# sdram.net
KiCad netlist of a schematic drawn in Altium Designer
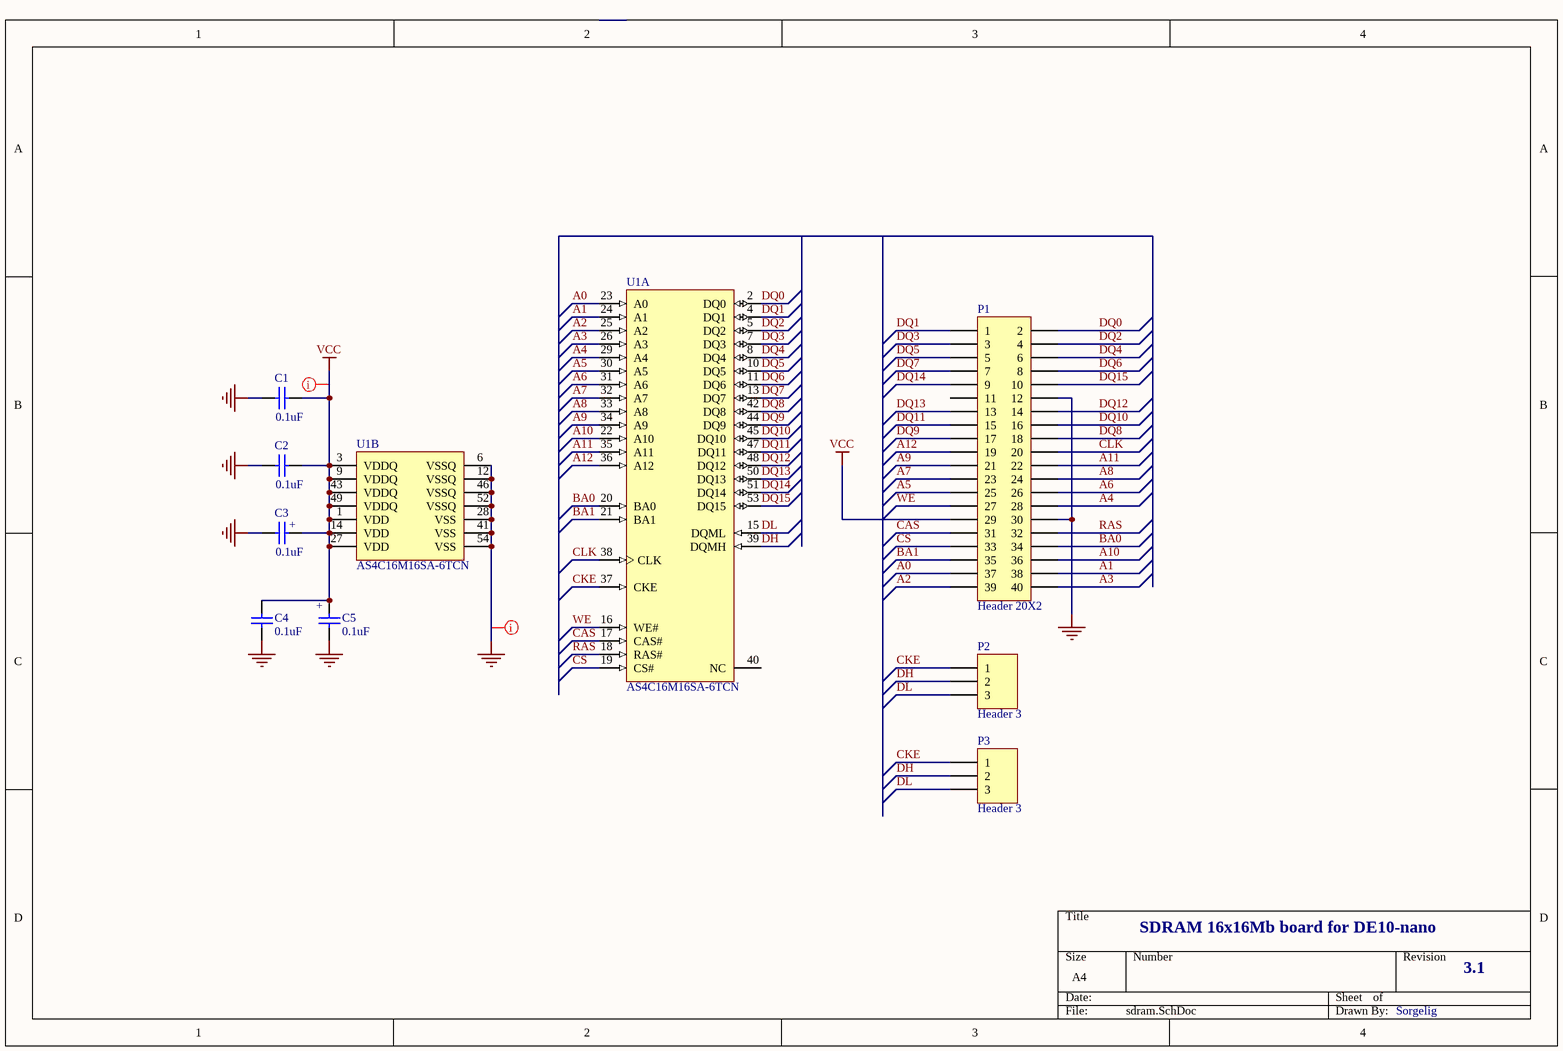
[diagram p0: sdram.SchDoc]

(export (version "E")
  (design (tool "Eeschema 10.0.6"))
  (components
    (comp (ref "C1")
      (value "0.1uF")
      (footprint "0805")
      (description "Ceramic Chip Capacitor - Standard")
      (fields (field (name "Comment") "C0805") (field (name "PUBLISHER") "Altium Limited"))
      (libsource (lib "KEMET Chip Capacitor") (part "C0805"))
    )
    (comp (ref "C2")
      (value "0.1uF")
      (footprint "0805")
      (description "Ceramic Chip Capacitor - Standard")
      (fields (field (name "Comment") "C0805") (field (name "PUBLISHER") "Altium Limited"))
      (libsource (lib "KEMET Chip Capacitor") (part "C0805"))
    )
    (comp (ref "C3")
      (value "+")
      (footprint "0805")
      (description "Ceramic Chip Capacitor - Standard")
      (fields (field (name "ALTIUM_VALUE") "0.1uF") (field (name "PUBLISHER") "Altium Limited"))
      (libsource (lib "KEMET Chip Capacitor") (part "C0805"))
    )
    (comp (ref "C4")
      (value "0.1uF")
      (footprint "0805")
      (description "Ceramic Chip Capacitor - Standard")
      (fields (field (name "Comment") "C0805") (field (name "PUBLISHER") "Altium Limited"))
      (libsource (lib "KEMET Chip Capacitor") (part "C0805"))
    )
    (comp (ref "C5")
      (value "+")
      (footprint "0805")
      (description "Ceramic Chip Capacitor - Standard")
      (fields (field (name "ALTIUM_VALUE") "0.1uF") (field (name "PUBLISHER") "Altium Limited"))
      (libsource (lib "KEMET Chip Capacitor") (part "C0805"))
    )
    (comp (ref "P1")
      (value "Header 20X2")
      (footprint "HDR2X20")
      (description "Header, 20-Pin, Dual row")
      (fields (field (name "PUBLISHER") "Altium Limited"))
      (libsource (lib "Miscellaneous Connectors") (part "Header 20X2"))
    )
    (comp (ref "P2")
      (value "Header 3")
      (footprint "HDR1X3")
      (description "Header, 3-Pin")
      (fields (field (name "PUBLISHER") "Altium Limited"))
      (libsource (lib "Miscellaneous Connectors") (part "Header 3"))
    )
    (comp (ref "P3")
      (value "Header 3")
      (footprint "HDR1X3")
      (description "Header, 3-Pin")
      (fields (field (name "PUBLISHER") "Altium Limited"))
      (libsource (lib "Miscellaneous Connectors") (part "Header 3"))
    )
    (comp (ref "U1")
      (value "AS4C16M16SA-6TCN")
      (footprint "MICT-P-54_N")
      (description "256Mb PC133 SDR SDRAM, 16Mb x 16, 6ns, 3.3V, 0 to 70 degC, 54-Pin TSOP, Pb-Free")
      (fields (field (name "VOLTAGE") "3.3V ") (field (name "MANUFACTURER") "Micron"))
      (libsource (lib "Micron Memory SDRAM") (part "MT48LC16M16A2P-6A"))
    )
  )
  (nets
    (net (code "1") (name "/A0") (class "Default")
      (node (ref "P1") (pin "37") (pinfunction "37_37") (pintype "passive"))
      (node (ref "U1") (pin "23") (pinfunction "A0_23") (pintype "input"))
    )
    (net (code "2") (name "/A1") (class "Default")
      (node (ref "P1") (pin "38") (pinfunction "38_38") (pintype "passive"))
      (node (ref "U1") (pin "24") (pinfunction "A1_24") (pintype "input"))
    )
    (net (code "3") (name "/A2") (class "Default")
      (node (ref "P1") (pin "39") (pinfunction "39_39") (pintype "passive"))
      (node (ref "U1") (pin "25") (pinfunction "A2_25") (pintype "input"))
    )
    (net (code "4") (name "/A3") (class "Default")
      (node (ref "P1") (pin "40") (pinfunction "40_40") (pintype "passive"))
      (node (ref "U1") (pin "26") (pinfunction "A3_26") (pintype "input"))
    )
    (net (code "5") (name "/A4") (class "Default")
      (node (ref "P1") (pin "28") (pinfunction "28_28") (pintype "passive"))
      (node (ref "U1") (pin "29") (pinfunction "A4_29") (pintype "input"))
    )
    (net (code "6") (name "/A5") (class "Default")
      (node (ref "P1") (pin "25") (pinfunction "25_25") (pintype "passive"))
      (node (ref "U1") (pin "30") (pinfunction "A5_30") (pintype "input"))
    )
    (net (code "7") (name "/A6") (class "Default")
      (node (ref "P1") (pin "26") (pinfunction "26_26") (pintype "passive"))
      (node (ref "U1") (pin "31") (pinfunction "A6_31") (pintype "input"))
    )
    (net (code "8") (name "/A7") (class "Default")
      (node (ref "P1") (pin "23") (pinfunction "23_23") (pintype "passive"))
      (node (ref "U1") (pin "32") (pinfunction "A7_32") (pintype "input"))
    )
    (net (code "9") (name "/A8") (class "Default")
      (node (ref "P1") (pin "24") (pinfunction "24_24") (pintype "passive"))
      (node (ref "U1") (pin "33") (pinfunction "A8_33") (pintype "input"))
    )
    (net (code "10") (name "/A9") (class "Default")
      (node (ref "P1") (pin "21") (pinfunction "21_21") (pintype "passive"))
      (node (ref "U1") (pin "34") (pinfunction "A9_34") (pintype "input"))
    )
    (net (code "11") (name "/A10") (class "Default")
      (node (ref "P1") (pin "36") (pinfunction "36_36") (pintype "passive"))
      (node (ref "U1") (pin "22") (pinfunction "A10_22") (pintype "input"))
    )
    (net (code "12") (name "/A11") (class "Default")
      (node (ref "P1") (pin "22") (pinfunction "22_22") (pintype "passive"))
      (node (ref "U1") (pin "35") (pinfunction "A11_35") (pintype "input"))
    )
    (net (code "13") (name "/A12") (class "Default")
      (node (ref "P1") (pin "19") (pinfunction "19_19") (pintype "passive"))
      (node (ref "U1") (pin "36") (pinfunction "A12_36") (pintype "input"))
    )
    (net (code "14") (name "/BA0") (class "Default")
      (node (ref "P1") (pin "34") (pinfunction "34_34") (pintype "passive"))
      (node (ref "U1") (pin "20") (pinfunction "BA0_20") (pintype "input"))
    )
    (net (code "15") (name "/BA1") (class "Default")
      (node (ref "P1") (pin "35") (pinfunction "35_35") (pintype "passive"))
      (node (ref "U1") (pin "21") (pinfunction "BA1_21") (pintype "input"))
    )
    (net (code "16") (name "/CAS") (class "Default")
      (node (ref "P1") (pin "31") (pinfunction "31_31") (pintype "passive"))
      (node (ref "U1") (pin "17") (pinfunction "CAS#_17") (pintype "input"))
    )
    (net (code "17") (name "/CKE") (class "Default")
      (node (ref "P2") (pin "1") (pinfunction "1_1") (pintype "passive"))
      (node (ref "P3") (pin "1") (pinfunction "1_1") (pintype "passive"))
      (node (ref "U1") (pin "37") (pinfunction "CKE_37") (pintype "input"))
    )
    (net (code "18") (name "/CLK") (class "Default")
      (node (ref "P1") (pin "20") (pinfunction "20_20") (pintype "passive"))
      (node (ref "U1") (pin "38") (pinfunction "CLK_38") (pintype "input"))
    )
    (net (code "19") (name "/CS") (class "Default")
      (node (ref "P1") (pin "33") (pinfunction "33_33") (pintype "passive"))
      (node (ref "U1") (pin "19") (pinfunction "CS#_19") (pintype "input"))
    )
    (net (code "20") (name "/DH") (class "Default")
      (node (ref "P2") (pin "2") (pinfunction "2_2") (pintype "passive"))
      (node (ref "P3") (pin "2") (pinfunction "2_2") (pintype "passive"))
      (node (ref "U1") (pin "39") (pinfunction "DQMH_39") (pintype "input"))
    )
    (net (code "21") (name "/DL") (class "Default")
      (node (ref "P2") (pin "3") (pinfunction "3_3") (pintype "passive"))
      (node (ref "P3") (pin "3") (pinfunction "3_3") (pintype "passive"))
      (node (ref "U1") (pin "15") (pinfunction "DQML_15") (pintype "input"))
    )
    (net (code "22") (name "/DQ0") (class "Default")
      (node (ref "P1") (pin "2") (pinfunction "2_2") (pintype "passive"))
      (node (ref "U1") (pin "2") (pinfunction "DQ0_2") (pintype "bidirectional"))
    )
    (net (code "23") (name "/DQ1") (class "Default")
      (node (ref "P1") (pin "1") (pinfunction "1_1") (pintype "passive"))
      (node (ref "U1") (pin "4") (pinfunction "DQ1_4") (pintype "bidirectional"))
    )
    (net (code "24") (name "/DQ2") (class "Default")
      (node (ref "P1") (pin "4") (pinfunction "4_4") (pintype "passive"))
      (node (ref "U1") (pin "5") (pinfunction "DQ2_5") (pintype "bidirectional"))
    )
    (net (code "25") (name "/DQ3") (class "Default")
      (node (ref "P1") (pin "3") (pinfunction "3_3") (pintype "passive"))
      (node (ref "U1") (pin "7") (pinfunction "DQ3_7") (pintype "bidirectional"))
    )
    (net (code "26") (name "/DQ4") (class "Default")
      (node (ref "P1") (pin "6") (pinfunction "6_6") (pintype "passive"))
      (node (ref "U1") (pin "8") (pinfunction "DQ4_8") (pintype "bidirectional"))
    )
    (net (code "27") (name "/DQ5") (class "Default")
      (node (ref "P1") (pin "5") (pinfunction "5_5") (pintype "passive"))
      (node (ref "U1") (pin "10") (pinfunction "DQ5_10") (pintype "bidirectional"))
    )
    (net (code "28") (name "/DQ6") (class "Default")
      (node (ref "P1") (pin "8") (pinfunction "8_8") (pintype "passive"))
      (node (ref "U1") (pin "11") (pinfunction "DQ6_11") (pintype "bidirectional"))
    )
    (net (code "29") (name "/DQ7") (class "Default")
      (node (ref "P1") (pin "7") (pinfunction "7_7") (pintype "passive"))
      (node (ref "U1") (pin "13") (pinfunction "DQ7_13") (pintype "bidirectional"))
    )
    (net (code "30") (name "/DQ8") (class "Default")
      (node (ref "P1") (pin "18") (pinfunction "18_18") (pintype "passive"))
      (node (ref "U1") (pin "42") (pinfunction "DQ8_42") (pintype "bidirectional"))
    )
    (net (code "31") (name "/DQ9") (class "Default")
      (node (ref "P1") (pin "17") (pinfunction "17_17") (pintype "passive"))
      (node (ref "U1") (pin "44") (pinfunction "DQ9_44") (pintype "bidirectional"))
    )
    (net (code "32") (name "/DQ10") (class "Default")
      (node (ref "P1") (pin "16") (pinfunction "16_16") (pintype "passive"))
      (node (ref "U1") (pin "45") (pinfunction "DQ10_45") (pintype "bidirectional"))
    )
    (net (code "33") (name "/DQ11") (class "Default")
      (node (ref "P1") (pin "15") (pinfunction "15_15") (pintype "passive"))
      (node (ref "U1") (pin "47") (pinfunction "DQ11_47") (pintype "bidirectional"))
    )
    (net (code "34") (name "/DQ12") (class "Default")
      (node (ref "P1") (pin "14") (pinfunction "14_14") (pintype "passive"))
      (node (ref "U1") (pin "48") (pinfunction "DQ12_48") (pintype "bidirectional"))
    )
    (net (code "35") (name "/DQ13") (class "Default")
      (node (ref "P1") (pin "13") (pinfunction "13_13") (pintype "passive"))
      (node (ref "U1") (pin "50") (pinfunction "DQ13_50") (pintype "bidirectional"))
    )
    (net (code "36") (name "/DQ14") (class "Default")
      (node (ref "P1") (pin "9") (pinfunction "9_9") (pintype "passive"))
      (node (ref "U1") (pin "51") (pinfunction "DQ14_51") (pintype "bidirectional"))
    )
    (net (code "37") (name "/DQ15") (class "Default")
      (node (ref "P1") (pin "10") (pinfunction "10_10") (pintype "passive"))
      (node (ref "U1") (pin "53") (pinfunction "DQ15_53") (pintype "bidirectional"))
    )
    (net (code "38") (name "/RAS") (class "Default")
      (node (ref "P1") (pin "32") (pinfunction "32_32") (pintype "passive"))
      (node (ref "U1") (pin "18") (pinfunction "RAS#_18") (pintype "input"))
    )
    (net (code "39") (name "/WE") (class "Default")
      (node (ref "P1") (pin "27") (pinfunction "27_27") (pintype "passive"))
      (node (ref "U1") (pin "16") (pinfunction "WE#_16") (pintype "input"))
    )
    (net (code "40") (name "GND") (class "Default")
      (node (ref "C1") (pin "1") (pinfunction "1_1") (pintype "passive"))
      (node (ref "C2") (pin "1") (pinfunction "1_1") (pintype "passive"))
      (node (ref "C3") (pin "1") (pinfunction "1_1") (pintype "passive"))
      (node (ref "C4") (pin "1") (pinfunction "1_1") (pintype "passive"))
      (node (ref "C5") (pin "1") (pinfunction "1_1") (pintype "passive"))
      (node (ref "P1") (pin "12") (pinfunction "12_12") (pintype "power_in"))
      (node (ref "P1") (pin "30") (pinfunction "30_30") (pintype "power_in"))
      (node (ref "U1") (pin "12") (pinfunction "VSSQ_12") (pintype "power_in"))
      (node (ref "U1") (pin "28") (pinfunction "VSS_28") (pintype "power_in"))
      (node (ref "U1") (pin "41") (pinfunction "VSS_41") (pintype "power_in"))
      (node (ref "U1") (pin "46") (pinfunction "VSSQ_46") (pintype "power_in"))
      (node (ref "U1") (pin "52") (pinfunction "VSSQ_52") (pintype "power_in"))
      (node (ref "U1") (pin "54") (pinfunction "VSS_54") (pintype "power_in"))
      (node (ref "U1") (pin "6") (pinfunction "VSSQ_6") (pintype "power_in"))
    )
    (net (code "41") (name "VCC") (class "Default")
      (node (ref "C1") (pin "2") (pinfunction "2_2") (pintype "passive"))
      (node (ref "C2") (pin "2") (pinfunction "2_2") (pintype "passive"))
      (node (ref "C3") (pin "2") (pinfunction "2_2") (pintype "passive"))
      (node (ref "C4") (pin "2") (pinfunction "2_2") (pintype "passive"))
      (node (ref "C5") (pin "2") (pinfunction "2_2") (pintype "passive"))
      (node (ref "P1") (pin "29") (pinfunction "29_29") (pintype "power_in"))
      (node (ref "U1") (pin "1") (pinfunction "VDD_1") (pintype "power_in"))
      (node (ref "U1") (pin "14") (pinfunction "VDD_14") (pintype "power_in"))
      (node (ref "U1") (pin "27") (pinfunction "VDD_27") (pintype "power_in"))
      (node (ref "U1") (pin "3") (pinfunction "VDDQ_3") (pintype "power_in"))
      (node (ref "U1") (pin "43") (pinfunction "VDDQ_43") (pintype "power_in"))
      (node (ref "U1") (pin "49") (pinfunction "VDDQ_49") (pintype "power_in"))
      (node (ref "U1") (pin "9") (pinfunction "VDDQ_9") (pintype "power_in"))
    )
    (net (code "42") (name "unconnected-(P1-Pad11)") (class "Default")
      (node (ref "P1") (pin "11") (pinfunction "11_11") (pintype "power_in"))
    )
    (net (code "43") (name "unconnected-(U1A-NC-Pad40)") (class "Default")
      (node (ref "U1") (pin "40") (pinfunction "NC_40") (pintype "passive"))
    )
  )
)
